# Audio.net
KiCad netlist of a schematic drawn in Altium Designer
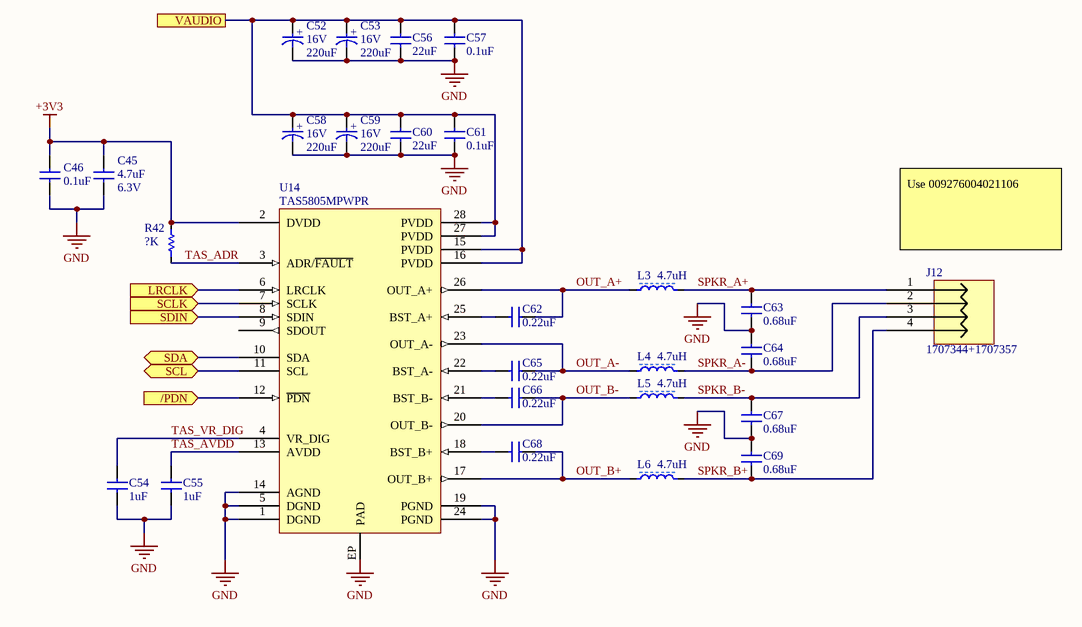
[diagram p0: Audio.SchDoc]

(export (version "E")
  (design (tool "Eeschema 10.0.6"))
  (components
    (comp (ref "C45")
      (value "4.7uF")
      (footprint "0603_Capacitor")
      (description "CAP CER 4.7UF 6.3V X5R 0603")
      (fields (field (name "VOLTAGE") "6.3V") (field (name "Comment") "CAP 4.7uF 6.3V X5R"))
      (libsource (lib "capacitor") (part "C_0603_4.7uF_6.3V_10%"))
    )
    (comp (ref "C46")
      (value "0.1uF")
      (footprint "0402_CAPACITOR")
      (description "CAP CERM 0.1uF 10% 16V 0402")
      (fields (field (name "VOLTAGE") "16V") (field (name "Comment") "CAP 0.1uF 16V X7R"))
      (libsource (lib "capacitor") (part "C_0402_0.1uF_16V_10%"))
    )
    (comp (ref "C52")
      (value "220uF")
      (footprint "CAP_6.3x8mm_SMD")
      (description "220µF 16V Aluminum Polymer Capacitor Radial, Can - SMD 22 mOhm 15000 Hrs @ 105°C")
      (fields
        (field (name "TOLERANCE") "20%")
        (field (name "MANUFACTURER PART NUMBER") "APXG160ARA221MF80G")
        (field (name "VOLTAGE RATING") "16V")
      )
      (libsource (lib "capacitor") (part "C_APXG160ARA221MF80G"))
    )
    (comp (ref "C53")
      (value "220uF")
      (footprint "CAP_6.3x8mm_SMD")
      (description "220µF 16V Aluminum Polymer Capacitor Radial, Can - SMD 22 mOhm 15000 Hrs @ 105°C")
      (fields
        (field (name "TOLERANCE") "20%")
        (field (name "MANUFACTURER PART NUMBER") "APXG160ARA221MF80G")
        (field (name "VOLTAGE RATING") "16V")
      )
      (libsource (lib "capacitor") (part "C_APXG160ARA221MF80G"))
    )
    (comp (ref "C54")
      (value "1uF")
      (footprint "0603_CAPACITOR")
      (description "CAP CERM 1uF 10% 16V 0603")
      (fields
        (field (name "VOLTAGE") "16V")
        (field (name "Comment") "CAP 1uF 16V X7R")
        (field (name "SVP CREATOR") "Spencer Berglund")
      )
      (libsource (lib "capacitor") (part "C_0603_1uF_16V_10%"))
    )
    (comp (ref "C55")
      (value "1uF")
      (footprint "0603_CAPACITOR")
      (description "CAP CERM 1uF 10% 16V 0603")
      (fields
        (field (name "VOLTAGE") "16V")
        (field (name "Comment") "CAP 1uF 16V X7R")
        (field (name "SVP CREATOR") "Spencer Berglund")
      )
      (libsource (lib "capacitor") (part "C_0603_1uF_16V_10%"))
    )
    (comp (ref "C56")
      (value "22uF")
      (footprint "0805_Capacitor")
      (description "CAP CERM 22uF 20% 16V 0805")
      (fields (field (name "VOLTAGE") "16V") (field (name "Comment") "CAP 22uF 16V X5R"))
      (libsource (lib "capacitor") (part "C_0805_22uF_16V_20%"))
    )
    (comp (ref "C57")
      (value "0.1uF")
      (footprint "0603_CAPACITOR")
      (description "CAP CERM 0.1uF 10% 50V 0603")
      (fields
        (field (name "VOLTAGE") "50V")
        (field (name "Comment") "CAP 0.1uF 50V X7R")
        (field (name "SVP CREATOR") "Spencer Berglund")
      )
      (libsource (lib "capacitor") (part "C_0603_0.1uF_50V_10%"))
    )
    (comp (ref "C58")
      (value "220uF")
      (footprint "CAP_6.3x8mm_SMD")
      (description "220µF 16V Aluminum Polymer Capacitor Radial, Can - SMD 22 mOhm 15000 Hrs @ 105°C")
      (fields
        (field (name "TOLERANCE") "20%")
        (field (name "MANUFACTURER PART NUMBER") "APXG160ARA221MF80G")
        (field (name "VOLTAGE RATING") "16V")
      )
      (libsource (lib "capacitor") (part "C_APXG160ARA221MF80G"))
    )
    (comp (ref "C59")
      (value "220uF")
      (footprint "CAP_6.3x8mm_SMD")
      (description "220µF 16V Aluminum Polymer Capacitor Radial, Can - SMD 22 mOhm 15000 Hrs @ 105°C")
      (fields
        (field (name "TOLERANCE") "20%")
        (field (name "MANUFACTURER PART NUMBER") "APXG160ARA221MF80G")
        (field (name "VOLTAGE RATING") "16V")
      )
      (libsource (lib "capacitor") (part "C_APXG160ARA221MF80G"))
    )
    (comp (ref "C60")
      (value "22uF")
      (footprint "0805_Capacitor")
      (description "CAP CERM 22uF 20% 16V 0805")
      (fields (field (name "VOLTAGE") "16V") (field (name "Comment") "CAP 22uF 16V X5R"))
      (libsource (lib "capacitor") (part "C_0805_22uF_16V_20%"))
    )
    (comp (ref "C61")
      (value "0.1uF")
      (footprint "0603_CAPACITOR")
      (description "CAP CERM 0.1uF 10% 50V 0603")
      (fields
        (field (name "VOLTAGE") "50V")
        (field (name "Comment") "CAP 0.1uF 50V X7R")
        (field (name "SVP CREATOR") "Spencer Berglund")
      )
      (libsource (lib "capacitor") (part "C_0603_0.1uF_50V_10%"))
    )
    (comp (ref "C62")
      (value "0.22uF")
      (footprint "0603_CAPACITOR")
      (description "CAP CER 0.22UF 25V X7R 0603")
      (fields (field (name "VOLTAGE") "25V") (field (name "Comment") "CAP 0.22uF 25V X7R"))
      (libsource (lib "capacitor") (part "C_0603_0.22uF_25V_10%"))
    )
    (comp (ref "C63")
      (value "0.68uF")
      (footprint "0805_Capacitor")
      (description "CAP CERM 0.68uF 10% 25V 0805")
      (fields (field (name "VOLTAGE") "25V") (field (name "Comment") "CAP 0.68uF 25V X7R"))
      (libsource (lib "capacitor") (part "C_0805_0.68uF_25V_10%"))
    )
    (comp (ref "C64")
      (value "0.68uF")
      (footprint "0805_Capacitor")
      (description "CAP CERM 0.68uF 10% 25V 0805")
      (fields (field (name "VOLTAGE") "25V") (field (name "Comment") "CAP 0.68uF 25V X7R"))
      (libsource (lib "capacitor") (part "C_0805_0.68uF_25V_10%"))
    )
    (comp (ref "C65")
      (value "0.22uF")
      (footprint "0603_CAPACITOR")
      (description "CAP CER 0.22UF 25V X7R 0603")
      (fields (field (name "VOLTAGE") "25V") (field (name "Comment") "CAP 0.22uF 25V X7R"))
      (libsource (lib "capacitor") (part "C_0603_0.22uF_25V_10%"))
    )
    (comp (ref "C66")
      (value "0.22uF")
      (footprint "0603_CAPACITOR")
      (description "CAP CER 0.22UF 25V X7R 0603")
      (fields (field (name "VOLTAGE") "25V") (field (name "Comment") "CAP 0.22uF 25V X7R"))
      (libsource (lib "capacitor") (part "C_0603_0.22uF_25V_10%"))
    )
    (comp (ref "C67")
      (value "0.68uF")
      (footprint "0805_Capacitor")
      (description "CAP CERM 0.68uF 10% 25V 0805")
      (fields (field (name "VOLTAGE") "25V") (field (name "Comment") "CAP 0.68uF 25V X7R"))
      (libsource (lib "capacitor") (part "C_0805_0.68uF_25V_10%"))
    )
    (comp (ref "C68")
      (value "0.22uF")
      (footprint "0603_CAPACITOR")
      (description "CAP CER 0.22UF 25V X7R 0603")
      (fields (field (name "VOLTAGE") "25V") (field (name "Comment") "CAP 0.22uF 25V X7R"))
      (libsource (lib "capacitor") (part "C_0603_0.22uF_25V_10%"))
    )
    (comp (ref "C69")
      (value "0.68uF")
      (footprint "0805_Capacitor")
      (description "CAP CERM 0.68uF 10% 25V 0805")
      (fields (field (name "VOLTAGE") "25V") (field (name "Comment") "CAP 0.68uF 25V X7R"))
      (libsource (lib "capacitor") (part "C_0805_0.68uF_25V_10%"))
    )
    (comp (ref "J12")
      (value "1707344+1707357")
      (footprint "Phoenix:1707344(3)+1707357(1)")
      (description "PCB terminal block ZFKDS 3.81mm vertical, 4 pin")
      (libsource (lib "phoenix") (part "J_PHOENIX_4T_3.81"))
    )
    (comp (ref "L3")
      (value "4.7uH")
      (footprint "L_SRN6045")
      (description "4.7µH Semi-Shielded Wirewound Inductor 4.5A 26mOhm Nonstandard")
      (fields
        (field (name "MANUFACTURER PART NUMBER") "SRN6045TA-4R7M")
        (field (name "MANUFACTURER") "Bourns")
      )
      (libsource (lib "inductor") (part "L_SRN6045TA-4R7M"))
    )
    (comp (ref "L4")
      (value "4.7uH")
      (footprint "L_SRN6045")
      (description "4.7µH Semi-Shielded Wirewound Inductor 4.5A 26mOhm Nonstandard")
      (fields
        (field (name "MANUFACTURER PART NUMBER") "SRN6045TA-4R7M")
        (field (name "MANUFACTURER") "Bourns")
      )
      (libsource (lib "inductor") (part "L_SRN6045TA-4R7M"))
    )
    (comp (ref "L5")
      (value "4.7uH")
      (footprint "L_SRN6045")
      (description "4.7µH Semi-Shielded Wirewound Inductor 4.5A 26mOhm Nonstandard")
      (fields
        (field (name "MANUFACTURER PART NUMBER") "SRN6045TA-4R7M")
        (field (name "MANUFACTURER") "Bourns")
      )
      (libsource (lib "inductor") (part "L_SRN6045TA-4R7M"))
    )
    (comp (ref "L6")
      (value "4.7uH")
      (footprint "L_SRN6045")
      (description "4.7µH Semi-Shielded Wirewound Inductor 4.5A 26mOhm Nonstandard")
      (fields
        (field (name "MANUFACTURER PART NUMBER") "SRN6045TA-4R7M")
        (field (name "MANUFACTURER") "Bourns")
      )
      (libsource (lib "inductor") (part "L_SRN6045TA-4R7M"))
    )
    (comp (ref "R42")
      (value "?K")
      (footprint "0402_Resistor")
      (description "Generic 0402 Resistor (10.2R to 10M)")
      (fields (field (name "TOLERANCE") "±1%") (field (name "MANUFACTURER") "Yageo"))
      (libsource (lib "resistor") (part "R_0402_generic_1%"))
    )
    (comp (ref "U14")
      (value "TAS5805MPWPR")
      (footprint "TSSOP-28-EP")
      (description "Amplifier IC 1-Channel (Mono) or 2-Channel (Stereo) Class D 28-HTSSOP")
      (fields (field (name "MANUFACTURER") "Texas Instruments"))
      (libsource (lib "ic") (part "U_TAS5805M"))
    )
  )
  (nets
    (net (code "1") (name "+3V3") (class "Default")
      (node (ref "C45") (pin "2") (pinfunction "2_2") (pintype "passive"))
      (node (ref "C46") (pin "1") (pinfunction "1_1") (pintype "passive"))
      (node (ref "R42") (pin "2") (pinfunction "2_2") (pintype "passive"))
      (node (ref "U14") (pin "2") (pinfunction "DVDD_2") (pintype "power_in"))
    )
    (net (code "2") (name "/LRCLK") (class "Default")
      (node (ref "U14") (pin "6") (pinfunction "LRCLK_6") (pintype "input"))
    )
    (net (code "3") (name "/OUT_A+") (class "Default")
      (node (ref "C62") (pin "1") (pinfunction "1_1") (pintype "passive"))
      (node (ref "L3") (pin "1") (pinfunction "1_1") (pintype "passive"))
      (node (ref "U14") (pin "26") (pinfunction "OUT_A+_26") (pintype "output"))
    )
    (net (code "4") (name "/OUT_A-") (class "Default")
      (node (ref "C65") (pin "1") (pinfunction "1_1") (pintype "passive"))
      (node (ref "L4") (pin "1") (pinfunction "1_1") (pintype "passive"))
      (node (ref "U14") (pin "23") (pinfunction "OUT_A-_23") (pintype "output"))
    )
    (net (code "5") (name "/OUT_B+") (class "Default")
      (node (ref "C68") (pin "1") (pinfunction "1_1") (pintype "passive"))
      (node (ref "L6") (pin "1") (pinfunction "1_1") (pintype "passive"))
      (node (ref "U14") (pin "17") (pinfunction "OUT_B+_17") (pintype "output"))
    )
    (net (code "6") (name "/OUT_B-") (class "Default")
      (node (ref "C66") (pin "1") (pinfunction "1_1") (pintype "passive"))
      (node (ref "L5") (pin "1") (pinfunction "1_1") (pintype "passive"))
      (node (ref "U14") (pin "20") (pinfunction "OUT_B-_20") (pintype "output"))
    )
    (net (code "7") (name "/SCL") (class "Default")
      (node (ref "U14") (pin "11") (pinfunction "SCL_11") (pintype "open_collector"))
    )
    (net (code "8") (name "/SCLK") (class "Default")
      (node (ref "U14") (pin "7") (pinfunction "SCLK_7") (pintype "input"))
    )
    (net (code "9") (name "/SDA") (class "Default")
      (node (ref "U14") (pin "10") (pinfunction "SDA_10") (pintype "open_collector"))
    )
    (net (code "10") (name "/SDIN") (class "Default")
      (node (ref "U14") (pin "8") (pinfunction "SDIN_8") (pintype "input"))
    )
    (net (code "11") (name "/SPKR_A+") (class "Default")
      (node (ref "C63") (pin "1") (pinfunction "1_1") (pintype "passive"))
      (node (ref "J12") (pin "1") (pinfunction "1_1") (pintype "passive"))
      (node (ref "L3") (pin "2") (pinfunction "2_2") (pintype "passive"))
    )
    (net (code "12") (name "/SPKR_A-") (class "Default")
      (node (ref "C64") (pin "2") (pinfunction "2_2") (pintype "passive"))
      (node (ref "J12") (pin "2") (pinfunction "2_2") (pintype "passive"))
      (node (ref "L4") (pin "2") (pinfunction "2_2") (pintype "passive"))
    )
    (net (code "13") (name "/SPKR_B+") (class "Default")
      (node (ref "C69") (pin "2") (pinfunction "2_2") (pintype "passive"))
      (node (ref "J12") (pin "4") (pinfunction "4_4") (pintype "passive"))
      (node (ref "L6") (pin "2") (pinfunction "2_2") (pintype "passive"))
    )
    (net (code "14") (name "/SPKR_B-") (class "Default")
      (node (ref "C67") (pin "1") (pinfunction "1_1") (pintype "passive"))
      (node (ref "J12") (pin "3") (pinfunction "3_3") (pintype "passive"))
      (node (ref "L5") (pin "2") (pinfunction "2_2") (pintype "passive"))
    )
    (net (code "15") (name "/TAS_ADR") (class "Default")
      (node (ref "R42") (pin "1") (pinfunction "1_1") (pintype "passive"))
      (node (ref "U14") (pin "3") (pinfunction "ADR/~{FAULT}_3") (pintype "input"))
    )
    (net (code "16") (name "/TAS_AVDD") (class "Default")
      (node (ref "C55") (pin "1") (pinfunction "1_1") (pintype "passive"))
      (node (ref "U14") (pin "13") (pinfunction "AVDD_13") (pintype "power_in"))
    )
    (net (code "17") (name "/TAS_VR_DIG") (class "Default")
      (node (ref "C54") (pin "1") (pinfunction "1_1") (pintype "passive"))
      (node (ref "U14") (pin "4") (pinfunction "VR_DIG_4") (pintype "power_in"))
    )
    (net (code "18") (name "/VAUDIO") (class "Default")
      (node (ref "C52") (pin "1") (pinfunction "1_1") (pintype "passive"))
      (node (ref "C53") (pin "1") (pinfunction "1_1") (pintype "passive"))
      (node (ref "C56") (pin "1") (pinfunction "1_1") (pintype "passive"))
      (node (ref "C57") (pin "1") (pinfunction "1_1") (pintype "passive"))
      (node (ref "C58") (pin "1") (pinfunction "1_1") (pintype "passive"))
      (node (ref "C59") (pin "1") (pinfunction "1_1") (pintype "passive"))
      (node (ref "C60") (pin "1") (pinfunction "1_1") (pintype "passive"))
      (node (ref "C61") (pin "1") (pinfunction "1_1") (pintype "passive"))
      (node (ref "U14") (pin "15") (pinfunction "PVDD_15") (pintype "power_in"))
      (node (ref "U14") (pin "16") (pinfunction "PVDD_16") (pintype "power_in"))
      (node (ref "U14") (pin "27") (pinfunction "PVDD_27") (pintype "power_in"))
      (node (ref "U14") (pin "28") (pinfunction "PVDD_28") (pintype "power_in"))
    )
    (net (code "19") (name "/{slash}PDN") (class "Default")
      (node (ref "U14") (pin "12") (pinfunction "~{PDN}_12") (pintype "input"))
    )
    (net (code "20") (name "GND") (class "Default")
      (node (ref "C45") (pin "1") (pinfunction "1_1") (pintype "passive"))
      (node (ref "C46") (pin "2") (pinfunction "2_2") (pintype "passive"))
      (node (ref "C52") (pin "2") (pinfunction "2_2") (pintype "passive"))
      (node (ref "C53") (pin "2") (pinfunction "2_2") (pintype "passive"))
      (node (ref "C54") (pin "2") (pinfunction "2_2") (pintype "passive"))
      (node (ref "C55") (pin "2") (pinfunction "2_2") (pintype "passive"))
      (node (ref "C56") (pin "2") (pinfunction "2_2") (pintype "passive"))
      (node (ref "C57") (pin "2") (pinfunction "2_2") (pintype "passive"))
      (node (ref "C58") (pin "2") (pinfunction "2_2") (pintype "passive"))
      (node (ref "C59") (pin "2") (pinfunction "2_2") (pintype "passive"))
      (node (ref "C60") (pin "2") (pinfunction "2_2") (pintype "passive"))
      (node (ref "C61") (pin "2") (pinfunction "2_2") (pintype "passive"))
      (node (ref "C63") (pin "2") (pinfunction "2_2") (pintype "passive"))
      (node (ref "C64") (pin "1") (pinfunction "1_1") (pintype "passive"))
      (node (ref "C67") (pin "2") (pinfunction "2_2") (pintype "passive"))
      (node (ref "C69") (pin "1") (pinfunction "1_1") (pintype "passive"))
      (node (ref "U14") (pin "1") (pinfunction "DGND_1") (pintype "power_in"))
      (node (ref "U14") (pin "14") (pinfunction "AGND_14") (pintype "power_in"))
      (node (ref "U14") (pin "19") (pinfunction "PGND_19") (pintype "power_in"))
      (node (ref "U14") (pin "24") (pinfunction "PGND_24") (pintype "power_in"))
      (node (ref "U14") (pin "5") (pinfunction "DGND_5") (pintype "power_in"))
      (node (ref "U14") (pin "EP") (pinfunction "PAD_EP") (pintype "power_in"))
    )
    (net (code "21") (name "Net-(U14-BST_A+)") (class "Default")
      (node (ref "C62") (pin "2") (pinfunction "2_2") (pintype "passive"))
      (node (ref "U14") (pin "25") (pinfunction "BST_A+_25") (pintype "input"))
    )
    (net (code "22") (name "Net-(U14-BST_A-)") (class "Default")
      (node (ref "C65") (pin "2") (pinfunction "2_2") (pintype "passive"))
      (node (ref "U14") (pin "22") (pinfunction "BST_A-_22") (pintype "input"))
    )
    (net (code "23") (name "Net-(U14-BST_B+)") (class "Default")
      (node (ref "C68") (pin "2") (pinfunction "2_2") (pintype "passive"))
      (node (ref "U14") (pin "18") (pinfunction "BST_B+_18") (pintype "input"))
    )
    (net (code "24") (name "Net-(U14-BST_B-)") (class "Default")
      (node (ref "C66") (pin "2") (pinfunction "2_2") (pintype "passive"))
      (node (ref "U14") (pin "21") (pinfunction "BST_B-_21") (pintype "input"))
    )
    (net (code "25") (name "unconnected-(U14-SDOUT-Pad9)") (class "Default")
      (node (ref "U14") (pin "9") (pinfunction "SDOUT_9") (pintype "output"))
    )
  )
)
